# F4_SPI.net
KiCad netlist of a schematic drawn in Altium Designer
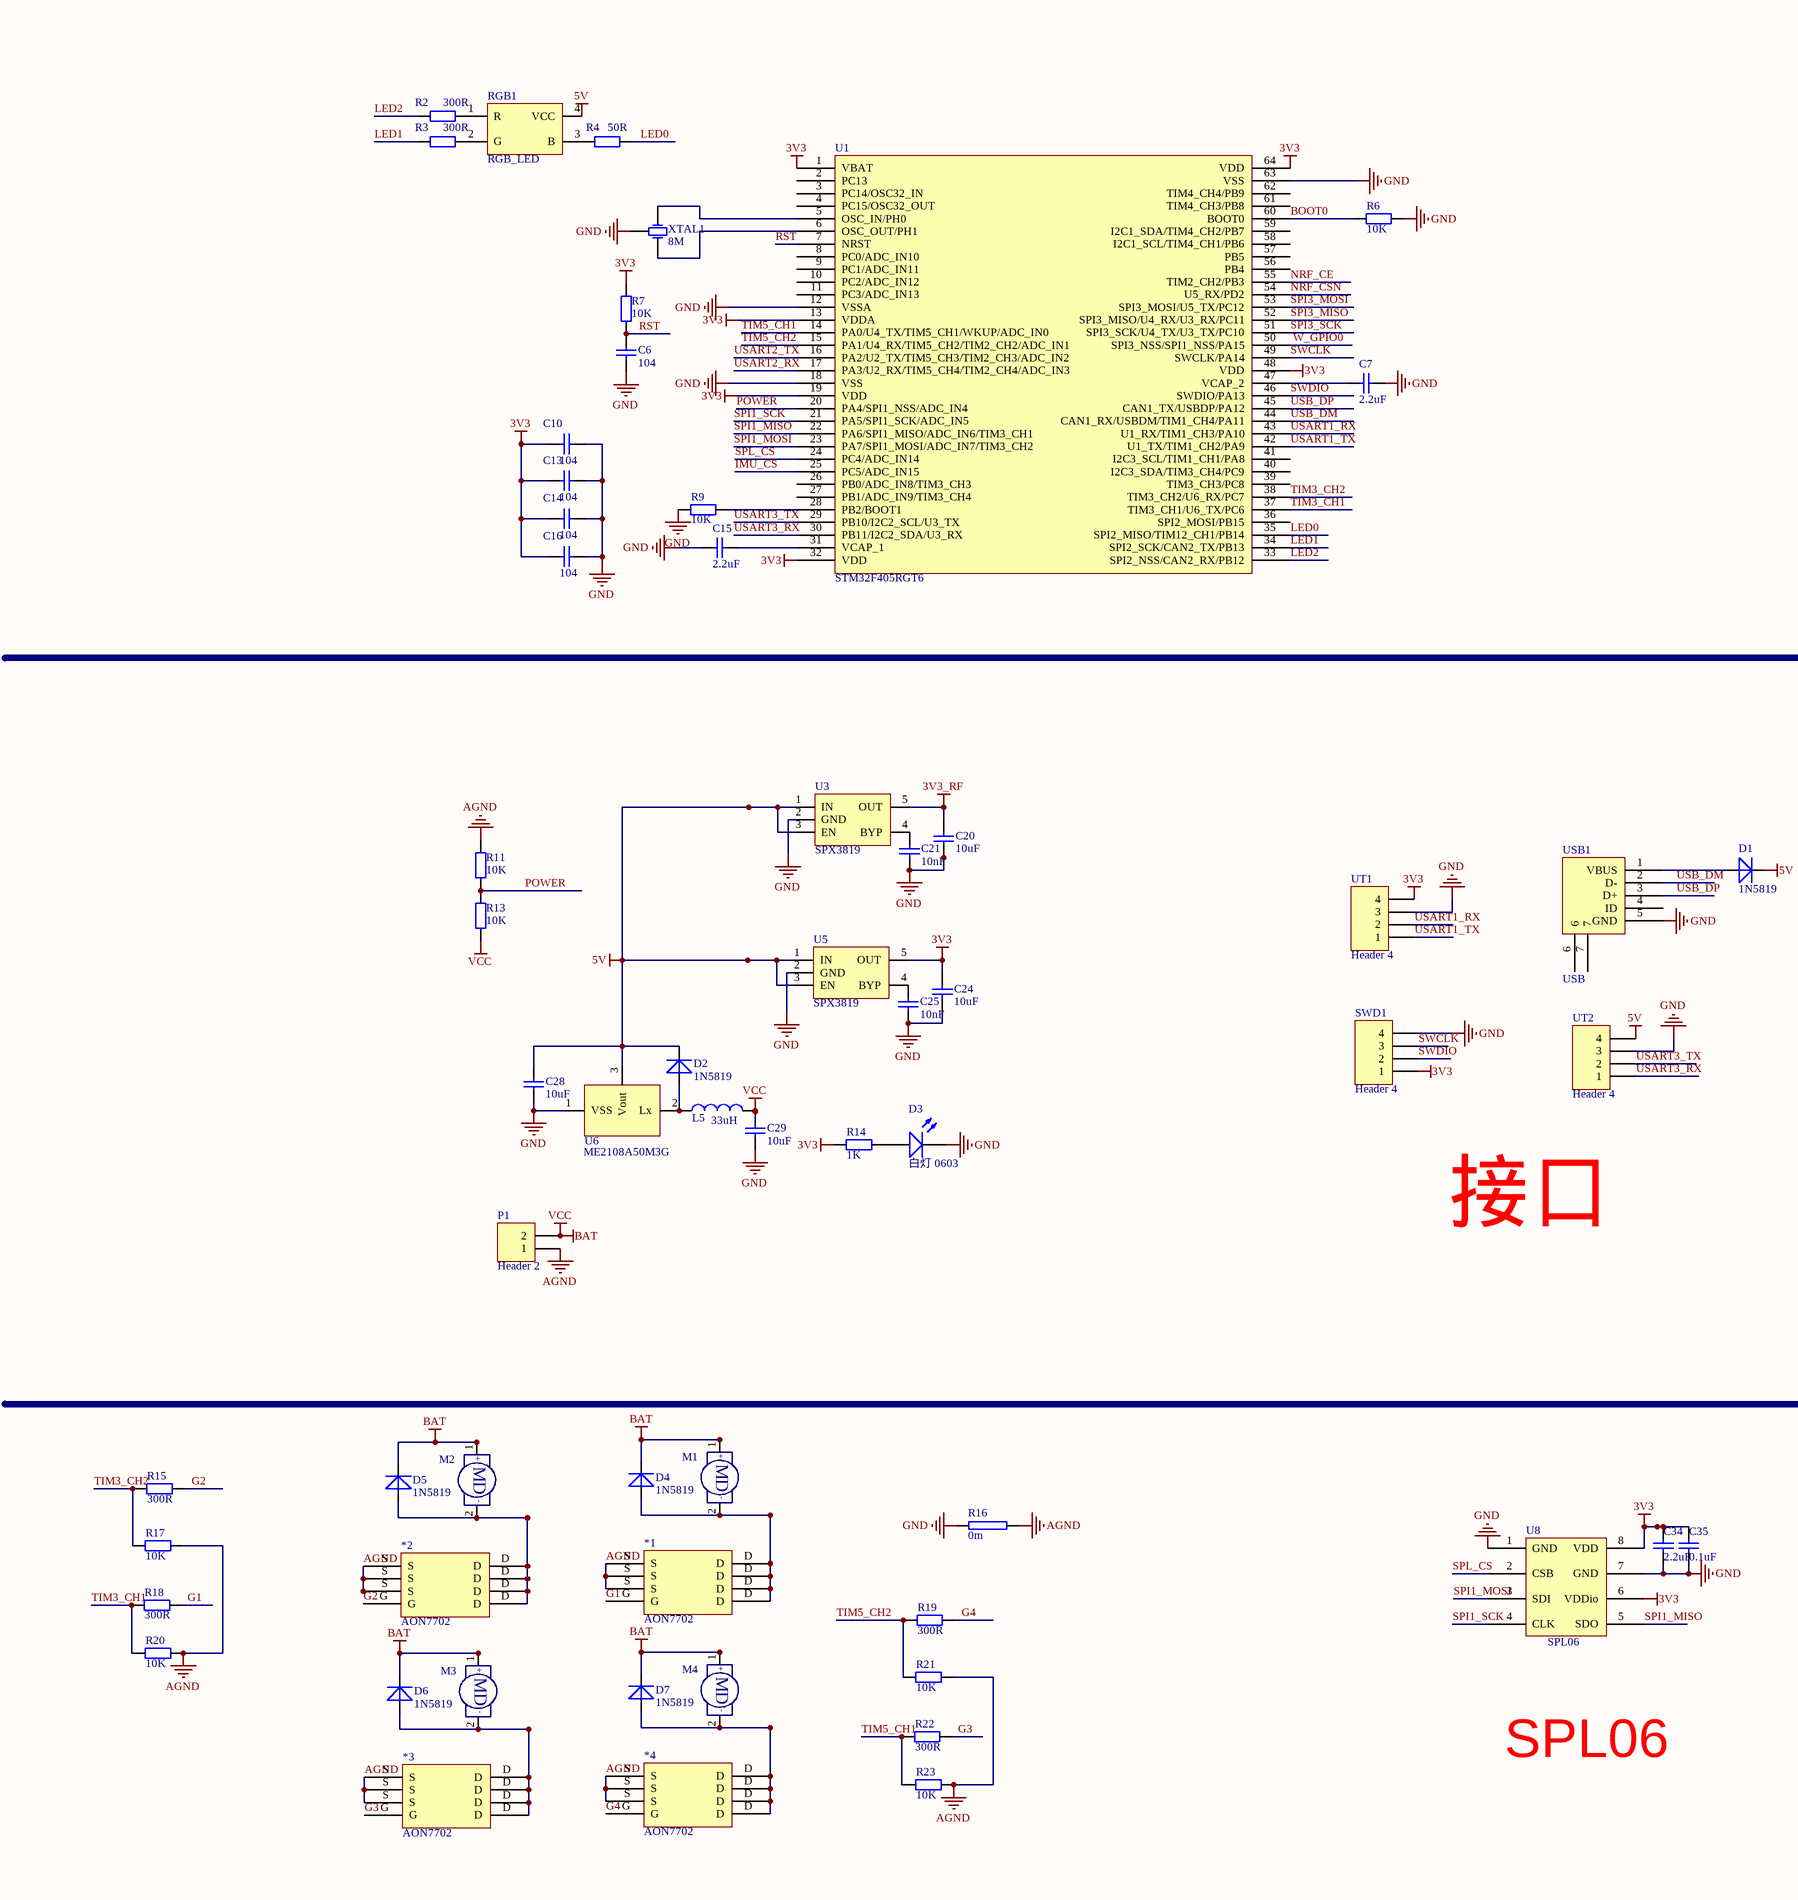
[diagram p0: F4_SPI.SchDoc, left]
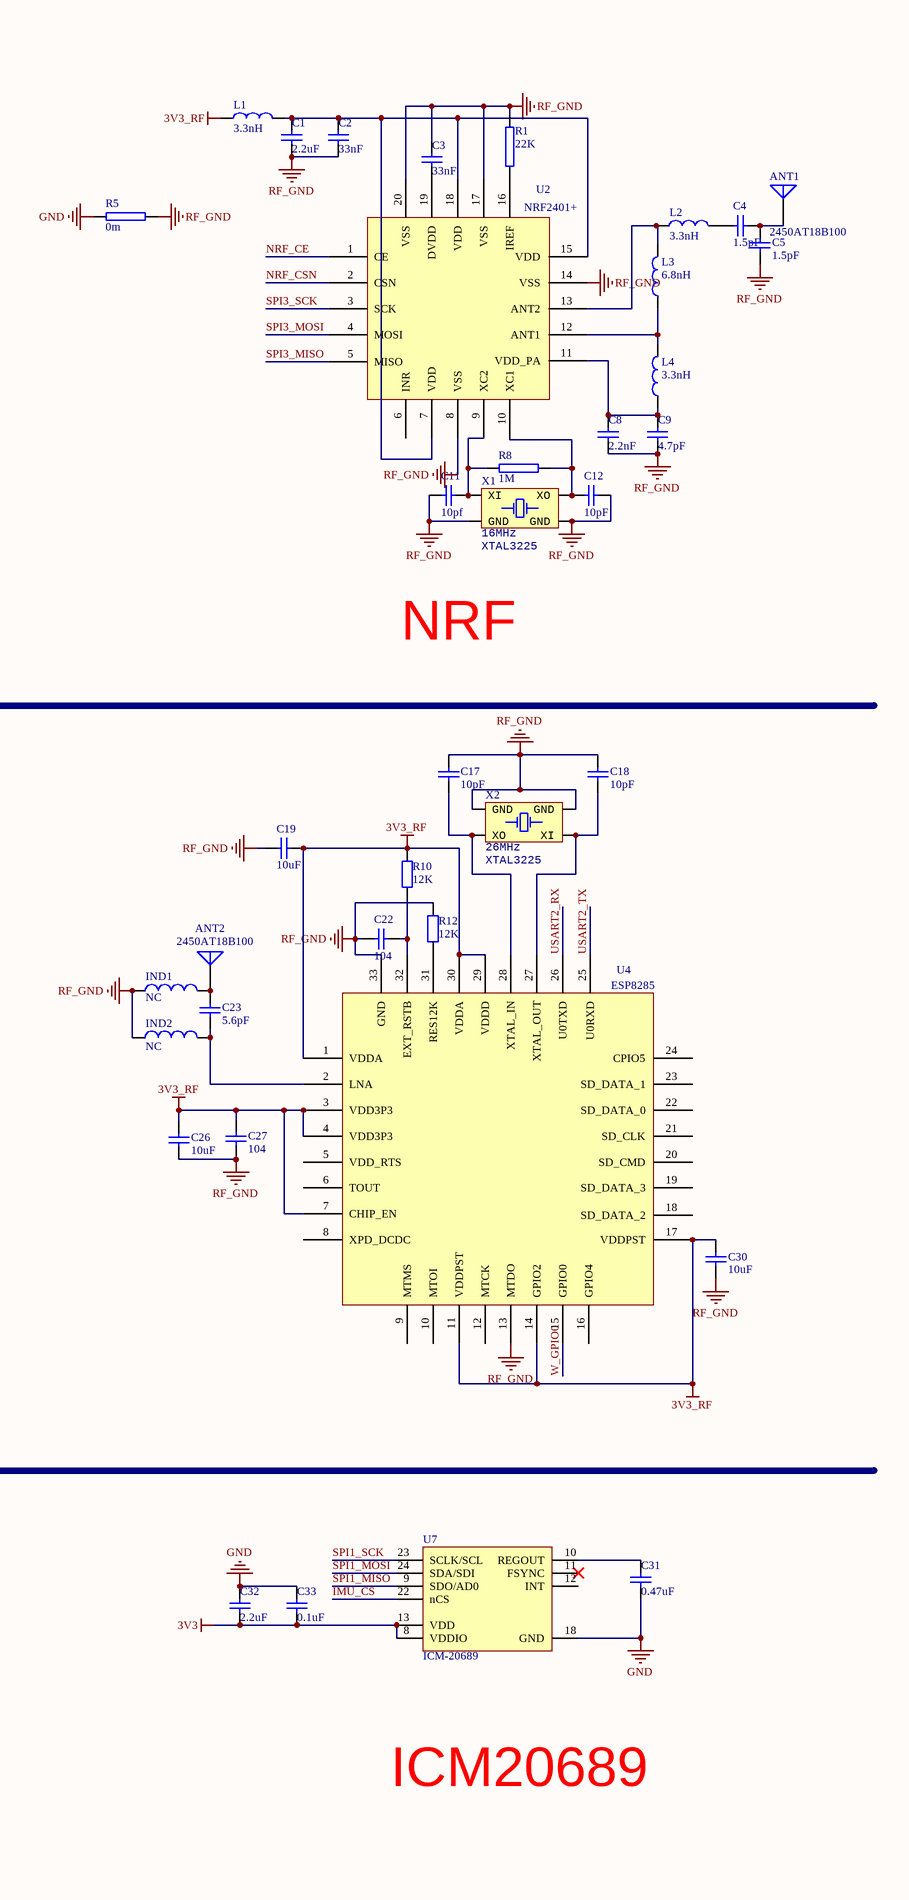
[diagram p1: F4_SPI.SchDoc, right]

(export (version "E")
  (design (tool "Eeschema 10.0.6"))
  (components
    (comp (ref "*1") (value "AON7702") (libsource (lib "XKZ") (part "AON7702")))
    (comp (ref "*2") (value "AON7702") (libsource (lib "XKZ") (part "AON7702")))
    (comp (ref "*3") (value "AON7702") (libsource (lib "XKZ") (part "AON7702")))
    (comp (ref "*4") (value "AON7702") (libsource (lib "XKZ") (part "AON7702")))
    (comp (ref "ANT1")
      (value "2450AT18B100")
      (footprint "2450AT18B100")
      (description "Generic Antenna")
      (libsource (lib "XKZ") (part "Antenna"))
    )
    (comp (ref "ANT2")
      (value "2450AT18B100")
      (footprint "2450AT18B100")
      (description "Generic Antenna")
      (libsource (lib "Miscellaneous Devices") (part "Antenna"))
    )
    (comp (ref "C1")
      (value "2.2uF")
      (footprint "0603_C")
      (description "Capacitor")
      (libsource (lib "Miscellaneous Devices") (part "Cap"))
    )
    (comp (ref "C2")
      (value "33nF")
      (footprint "0603_C")
      (description "Capacitor")
      (libsource (lib "Miscellaneous Devices") (part "Cap"))
    )
    (comp (ref "C3")
      (value "33nF")
      (footprint "0603_C")
      (description "Capacitor")
      (libsource (lib "Miscellaneous Devices") (part "Cap"))
    )
    (comp (ref "C4")
      (value "1.5pF")
      (footprint "0603_C")
      (description "Capacitor")
      (libsource (lib "Miscellaneous Devices") (part "Cap"))
    )
    (comp (ref "C5")
      (value "1.5pF")
      (footprint "0603_C")
      (description "Capacitor")
      (libsource (lib "Miscellaneous Devices") (part "Cap"))
    )
    (comp (ref "C6")
      (value "104")
      (footprint "0603_C")
      (description "Capacitor")
      (libsource (lib "Miscellaneous Devices") (part "Cap"))
    )
    (comp (ref "C7")
      (value "2.2uF")
      (footprint "0603_C")
      (description "Capacitor")
      (libsource (lib "Miscellaneous Devices") (part "Cap"))
    )
    (comp (ref "C8")
      (value "2.2nF")
      (footprint "0603_C")
      (description "Capacitor")
      (libsource (lib "Miscellaneous Devices") (part "Cap"))
    )
    (comp (ref "C9")
      (value "4.7pF")
      (footprint "0603_C")
      (description "Capacitor")
      (libsource (lib "Miscellaneous Devices") (part "Cap"))
    )
    (comp (ref "C10")
      (value "104")
      (footprint "0603_C")
      (description "Capacitor")
      (libsource (lib "Miscellaneous Devices") (part "Cap"))
    )
    (comp (ref "C11")
      (value "10pf")
      (footprint "0603_C")
      (description "Capacitor")
      (fields (field (name "Comment") "10pF"))
      (libsource (lib "Miscellaneous Devices") (part "Cap"))
    )
    (comp (ref "C12")
      (value "10pF")
      (footprint "0603_C")
      (description "Capacitor")
      (libsource (lib "Miscellaneous Devices") (part "Cap"))
    )
    (comp (ref "C13")
      (value "104")
      (footprint "0603_C")
      (description "Capacitor")
      (libsource (lib "Miscellaneous Devices") (part "Cap"))
    )
    (comp (ref "C14")
      (value "104")
      (footprint "0603_C")
      (description "Capacitor")
      (libsource (lib "Miscellaneous Devices") (part "Cap"))
    )
    (comp (ref "C15")
      (value "2.2uF")
      (footprint "0603_C")
      (description "Capacitor")
      (libsource (lib "Miscellaneous Devices") (part "Cap"))
    )
    (comp (ref "C16")
      (value "104")
      (footprint "0603_C")
      (description "Capacitor")
      (libsource (lib "Miscellaneous Devices") (part "Cap"))
    )
    (comp (ref "C17")
      (value "10pF")
      (footprint "0603_C")
      (description "Capacitor")
      (libsource (lib "Miscellaneous Devices") (part "Cap"))
    )
    (comp (ref "C18")
      (value "10pF")
      (footprint "0603_C")
      (description "Capacitor")
      (libsource (lib "Miscellaneous Devices") (part "Cap"))
    )
    (comp (ref "C19")
      (value "10uF")
      (footprint "0603_C")
      (description "Capacitor")
      (fields (field (name "Comment") "10uf"))
      (libsource (lib "Miscellaneous Devices") (part "Cap"))
    )
    (comp (ref "C20")
      (value "10uF")
      (footprint "0603_C")
      (description "Capacitor")
      (libsource (lib "Miscellaneous Devices") (part "Cap"))
    )
    (comp (ref "C21")
      (value "10nF")
      (footprint "0603_C")
      (description "Capacitor")
      (libsource (lib "Miscellaneous Devices") (part "Cap"))
    )
    (comp (ref "C22")
      (value "104")
      (footprint "0603_C")
      (description "Capacitor")
      (libsource (lib "Miscellaneous Devices") (part "Cap"))
    )
    (comp (ref "C23")
      (value "5.6pF")
      (footprint "0603_C")
      (description "Capacitor")
      (libsource (lib "Miscellaneous Devices") (part "Cap"))
    )
    (comp (ref "C24")
      (value "10uF")
      (footprint "0603_C")
      (description "Capacitor")
      (libsource (lib "Miscellaneous Devices") (part "Cap"))
    )
    (comp (ref "C25")
      (value "10nF")
      (footprint "0603_C")
      (description "Capacitor")
      (libsource (lib "Miscellaneous Devices") (part "Cap"))
    )
    (comp (ref "C26")
      (value "10uF")
      (footprint "0603_C")
      (description "Capacitor")
      (libsource (lib "Miscellaneous Devices") (part "Cap"))
    )
    (comp (ref "C27")
      (value "104")
      (footprint "0603_C")
      (description "Capacitor")
      (libsource (lib "Miscellaneous Devices") (part "Cap"))
    )
    (comp (ref "C28")
      (value "10uF")
      (footprint "1206_C")
      (description "Capacitor")
      (libsource (lib "Miscellaneous Devices") (part "Cap"))
    )
    (comp (ref "C29")
      (value "10uF")
      (footprint "1206_C")
      (description "Capacitor")
      (libsource (lib "Miscellaneous Devices") (part "Cap"))
    )
    (comp (ref "C30")
      (value "10uF")
      (footprint "0603_C")
      (description "Capacitor")
      (libsource (lib "Miscellaneous Devices") (part "Cap"))
    )
    (comp (ref "C31")
      (value "0.47uF")
      (footprint "0603_C")
      (description "Capacitor")
      (fields (field (name "Comment") "0.47uf"))
      (libsource (lib "Miscellaneous Devices") (part "Cap"))
    )
    (comp (ref "C32")
      (value "2.2uF")
      (footprint "0603_C")
      (description "Capacitor")
      (fields (field (name "Comment") "10uF"))
      (libsource (lib "Miscellaneous Devices") (part "Cap"))
    )
    (comp (ref "C33")
      (value "0.1uF")
      (footprint "0603_C")
      (description "Capacitor")
      (fields (field (name "Comment") "104"))
      (libsource (lib "Miscellaneous Devices") (part "Cap"))
    )
    (comp (ref "C34")
      (value "2.2uF")
      (footprint "0603_C")
      (description "Capacitor")
      (fields (field (name "Comment") "10uf"))
      (libsource (lib "Miscellaneous Devices") (part "Cap"))
    )
    (comp (ref "C35")
      (value "0.1uF")
      (footprint "0603_C")
      (description "Capacitor")
      (fields (field (name "Comment") "104"))
      (libsource (lib "Miscellaneous Devices") (part "Cap"))
    )
    (comp (ref "D1")
      (value "1N5819")
      (footprint "SOD-323")
      (description "二极管")
      (libsource (lib "NT-SchLibrary") (part "1N4007"))
    )
    (comp (ref "D2")
      (value "1N5819")
      (footprint "SOD-323")
      (description "二极管")
      (libsource (lib "NT-SchLibrary") (part "1N4007"))
    )
    (comp (ref "D3")
      (value "白灯 0603")
      (footprint "0603_LED_S1")
      (description "发光二极管")
      (libsource (lib "Miscellaneous Devices LC") (part "0603 白灯"))
    )
    (comp (ref "D4")
      (value "1N5819")
      (footprint "SOD-323")
      (description "二极管")
      (libsource (lib "NT-SchLibrary") (part "1N4007"))
    )
    (comp (ref "D5")
      (value "1N5819")
      (footprint "SOD-323")
      (description "二极管")
      (libsource (lib "NT-SchLibrary") (part "1N4007"))
    )
    (comp (ref "D6")
      (value "1N5819")
      (footprint "SOD-323")
      (description "二极管")
      (libsource (lib "NT-SchLibrary") (part "1N4007"))
    )
    (comp (ref "D7")
      (value "1N5819")
      (footprint "SOD-323")
      (description "二极管")
      (libsource (lib "NT-SchLibrary") (part "1N4007"))
    )
    (comp (ref "IND1")
      (value "NC")
      (footprint "0603_C")
      (description "Inductor")
      (libsource (lib "Miscellaneous Devices") (part "Inductor"))
    )
    (comp (ref "IND2")
      (value "NC")
      (footprint "0603_C")
      (description "Inductor")
      (libsource (lib "Miscellaneous Devices") (part "Inductor"))
    )
    (comp (ref "L1")
      (value "3.3nH")
      (footprint "0603_L")
      (description "电感")
      (libsource (lib "") (part "L1_1"))
    )
    (comp (ref "L2")
      (value "3.3nH")
      (footprint "0603_L")
      (description "电感")
      (libsource (lib "") (part "L1_1"))
    )
    (comp (ref "L3")
      (value "6.8nH")
      (footprint "0603_L")
      (description "电感")
      (libsource (lib "XKZ") (part "L1"))
    )
    (comp (ref "L4")
      (value "3.3nH")
      (footprint "0603_L")
      (description "电感")
      (libsource (lib "XKZ") (part "L1"))
    )
    (comp (ref "L5")
      (value "33uH")
      (footprint "CD32")
      (description "Inductor")
      (libsource (lib "Miscellaneous Devices") (part "Inductor"))
    )
    (comp (ref "M1")
      (value "Motor")
      (footprint "HDR1X2")
      (description "直流电机")
      (libsource (lib "NT-SchLibrary") (part "Motor"))
    )
    (comp (ref "M2")
      (value "Motor")
      (footprint "HDR1X2")
      (description "直流电机")
      (libsource (lib "NT-SchLibrary") (part "Motor"))
    )
    (comp (ref "M3")
      (value "Motor")
      (footprint "HDR1X2")
      (description "直流电机")
      (libsource (lib "NT-SchLibrary") (part "Motor"))
    )
    (comp (ref "M4")
      (value "Motor")
      (footprint "HDR1X2")
      (description "直流电机")
      (libsource (lib "NT-SchLibrary") (part "Motor"))
    )
    (comp (ref "P1")
      (value "Header 2")
      (footprint "HDR1X2")
      (description "Header, 2-Pin")
      (libsource (lib "FourRotorV2_schlib") (part "Header 2"))
    )
    (comp (ref "R1") (value "22K") (footprint "0603_R") (libsource (lib "XKZ") (part "RES")))
    (comp (ref "R2")
      (value "300R")
      (footprint "0603_R")
      (description "Resistor")
      (fields (field (name "Comment") "1K"))
      (libsource (lib "Miscellaneous Devices") (part "Res2"))
    )
    (comp (ref "R3")
      (value "300R")
      (footprint "0603_R")
      (description "Resistor")
      (fields (field (name "Comment") "1K"))
      (libsource (lib "Miscellaneous Devices") (part "Res2"))
    )
    (comp (ref "R4")
      (value "50R")
      (footprint "0603_R")
      (description "Resistor")
      (fields (field (name "Comment") "1K"))
      (libsource (lib "Miscellaneous Devices") (part "Res2"))
    )
    (comp (ref "R5") (value "0m") (footprint "0603_R") (libsource (lib "XKZ") (part "RES")))
    (comp (ref "R6")
      (value "10K")
      (footprint "0603_R")
      (description "Resistor")
      (libsource (lib "") (part "Res2_1"))
    )
    (comp (ref "R7")
      (value "10K")
      (footprint "0603_R")
      (description "Resistor")
      (libsource (lib "") (part "Res2_2"))
    )
    (comp (ref "R8") (value "1M") (footprint "0603_R") (libsource (lib "XKZ") (part "RES")))
    (comp (ref "R9")
      (value "10K")
      (footprint "0603_R")
      (description "Resistor")
      (libsource (lib "") (part "Res2_1"))
    )
    (comp (ref "R10")
      (value "12K")
      (footprint "0603_R")
      (description "Resistor")
      (libsource (lib "") (part "Res2_2"))
    )
    (comp (ref "R11")
      (value "10K")
      (footprint "0603_R")
      (description "Resistor")
      (libsource (lib "") (part "Res2_2"))
    )
    (comp (ref "R12")
      (value "12K")
      (footprint "0603_R")
      (description "Resistor")
      (libsource (lib "") (part "Res2_2"))
    )
    (comp (ref "R13")
      (value "10K")
      (footprint "0603_R")
      (description "Resistor")
      (libsource (lib "") (part "Res2_2"))
    )
    (comp (ref "R14")
      (value "1K")
      (footprint "0603_R")
      (description "Resistor")
      (libsource (lib "") (part "Res2_1"))
    )
    (comp (ref "R15")
      (value "300R")
      (footprint "0603_R")
      (description "Resistor")
      (libsource (lib "Miscellaneous Devices") (part "Res2"))
    )
    (comp (ref "R16") (value "0m") (footprint "0603_R") (libsource (lib "XKZ") (part "RES")))
    (comp (ref "R17")
      (value "10K")
      (footprint "0603_R")
      (description "Resistor")
      (libsource (lib "Miscellaneous Devices") (part "Res2"))
    )
    (comp (ref "R18")
      (value "300R")
      (footprint "0603_R")
      (description "Resistor")
      (libsource (lib "Miscellaneous Devices") (part "Res2"))
    )
    (comp (ref "R19")
      (value "300R")
      (footprint "0603_R")
      (description "Resistor")
      (libsource (lib "Miscellaneous Devices") (part "Res2"))
    )
    (comp (ref "R20")
      (value "10K")
      (footprint "0603_R")
      (description "Resistor")
      (libsource (lib "Miscellaneous Devices") (part "Res2"))
    )
    (comp (ref "R21")
      (value "10K")
      (footprint "0603_R")
      (description "Resistor")
      (libsource (lib "Miscellaneous Devices") (part "Res2"))
    )
    (comp (ref "R22")
      (value "300R")
      (footprint "0603_R")
      (description "Resistor")
      (libsource (lib "Miscellaneous Devices") (part "Res2"))
    )
    (comp (ref "R23")
      (value "10K")
      (footprint "0603_R")
      (description "Resistor")
      (libsource (lib "Miscellaneous Devices") (part "Res2"))
    )
    (comp (ref "RGB1")
      (value "RGB_LED")
      (footprint "LED_3528_RGB")
      (description "三色高亮LED")
      (libsource (lib "NT-SchLibrary") (part "RGB_LED"))
    )
    (comp (ref "SWD1")
      (value "Header 4")
      (footprint "SIP 1.25")
      (description "Header, 4-Pin")
      (libsource (lib "Miscellaneous Connectors") (part "Header 4"))
    )
    (comp (ref "U1")
      (value "STM32F405RGT6")
      (footprint "LQFP64 10x10_N")
      (description "Flaah:256/RAM:48/IO:51")
      (libsource (lib "ATKF405 V1.1") (part "STM32F405RGT6"))
    )
    (comp (ref "U2")
      (value "NRF2401+")
      (footprint "QFN20 4x4_N")
      (libsource (lib "NT-SchLibrary") (part "NRF2401+"))
    )
    (comp (ref "U3")
      (value "SPX3819")
      (footprint "SOT23-5N")
      (description "3.3V 降压芯片")
      (libsource (lib "NT-SchLibrary") (part "MIC5219"))
    )
    (comp (ref "U4")
      (value "ESP8285")
      (footprint "QFN32 5x5_M")
      (description "ESP8266")
      (libsource (lib "NT-SchLibrary") (part "ESP8266"))
    )
    (comp (ref "U5")
      (value "SPX3819")
      (footprint "SOT23-5N")
      (description "3.3V 降压芯片")
      (libsource (lib "NT-SchLibrary") (part "MIC5219"))
    )
    (comp (ref "U6")
      (value "ME2108A50M3G")
      (footprint "SOT23-3N")
      (description "5升压芯片")
      (libsource (lib "NT-SchLibrary") (part "ME2108A50M3G"))
    )
    (comp (ref "U7")
      (value "ICM-20689")
      (footprint "QFN24 4x4_M")
      (libsource (lib "schlib_by_wjy") (part "ICM-20689"))
    )
    (comp (ref "U8") (value "SPL06") (footprint "BMP280") (libsource (lib "NT-SchLibrary") (part "BMP280")))
    (comp (ref "USB1") (value "USB") (footprint "USB-MICRO_D") (libsource (lib "XKZ") (part "USB")))
    (comp (ref "UT1")
      (value "Header 4")
      (footprint "XKZ:SIP 1.25")
      (description "Header, 4-Pin")
      (libsource (lib "XKZ") (part "Header 4"))
    )
    (comp (ref "UT2")
      (value "Header 4")
      (footprint "SIP 1.25")
      (description "Header, 4-Pin")
      (libsource (lib "XKZ") (part "Header 4"))
    )
    (comp (ref "X1")
      (value "16MHz")
      (footprint "XT_3225_4")
      (description "Crystal Oscillator")
      (fields (field (name "TYPE") "XTAL3225"))
      (libsource (lib "") (part "XTAL_3225_4P_1"))
    )
    (comp (ref "X2")
      (value "26MHz")
      (footprint "XT_3225_4")
      (description "Crystal Oscillator")
      (fields (field (name "TYPE") "XTAL3225"))
      (libsource (lib "XKZ") (part "XTAL_3225_4P"))
    )
    (comp (ref "XTAL1")
      (value "8M")
      (footprint "XTAL-3215-3P")
      (libsource (lib "NT-SchLibrary") (part "XTAL1"))
    )
  )
  (nets
    (net (code "1") (name "/BOOT0") (class "Default")
      (node (ref "R6") (pin "2") (pinfunction "2_2") (pintype "passive"))
      (node (ref "U1") (pin "60") (pinfunction "BOOT0_60") (pintype "passive"))
    )
    (net (code "2") (name "/G1") (class "Default")
      (node (ref "*1") (pin "G") (pinfunction "G_G") (pintype "power_in"))
      (node (ref "R18") (pin "2") (pinfunction "2_2") (pintype "passive"))
    )
    (net (code "3") (name "/G2") (class "Default")
      (node (ref "*2") (pin "G") (pinfunction "G_G") (pintype "power_in"))
      (node (ref "R15") (pin "2") (pinfunction "2_2") (pintype "passive"))
    )
    (net (code "4") (name "/G3") (class "Default")
      (node (ref "*3") (pin "G") (pinfunction "G_G") (pintype "power_in"))
      (node (ref "R22") (pin "2") (pinfunction "2_2") (pintype "passive"))
    )
    (net (code "5") (name "/G4") (class "Default")
      (node (ref "*4") (pin "G") (pinfunction "G_G") (pintype "power_in"))
      (node (ref "R19") (pin "2") (pinfunction "2_2") (pintype "passive"))
    )
    (net (code "6") (name "/IMU_CS") (class "Default")
      (node (ref "U1") (pin "25") (pinfunction "PC5/ADC_IN15_25") (pintype "passive"))
      (node (ref "U7") (pin "22") (pinfunction "nCS_22") (pintype "passive"))
    )
    (net (code "7") (name "/LED0") (class "Default")
      (node (ref "R4") (pin "2") (pinfunction "2_2") (pintype "passive"))
      (node (ref "U1") (pin "35") (pinfunction "SPI2_MISO/TIM12_CH1/PB14_35") (pintype "passive"))
    )
    (net (code "8") (name "/LED1") (class "Default")
      (node (ref "R3") (pin "1") (pinfunction "1_1") (pintype "passive"))
      (node (ref "U1") (pin "34") (pinfunction "SPI2_SCK/CAN2_TX/PB13_34") (pintype "passive"))
    )
    (net (code "9") (name "/LED2") (class "Default")
      (node (ref "R2") (pin "1") (pinfunction "1_1") (pintype "passive"))
      (node (ref "U1") (pin "33") (pinfunction "SPI2_NSS/CAN2_RX/PB12_33") (pintype "passive"))
    )
    (net (code "10") (name "/NRF_CE") (class "Default")
      (node (ref "U1") (pin "55") (pinfunction "TIM2_CH2/PB3_55") (pintype "passive"))
      (node (ref "U2") (pin "1") (pinfunction "CE_1") (pintype "passive"))
    )
    (net (code "11") (name "/NRF_CSN") (class "Default")
      (node (ref "U1") (pin "54") (pinfunction "U5_RX/PD2_54") (pintype "passive"))
      (node (ref "U2") (pin "2") (pinfunction "CSN_2") (pintype "passive"))
    )
    (net (code "12") (name "/POWER") (class "Default")
      (node (ref "R11") (pin "2") (pinfunction "2_2") (pintype "passive"))
      (node (ref "R13") (pin "1") (pinfunction "1_1") (pintype "passive"))
      (node (ref "U1") (pin "20") (pinfunction "PA4/SPI1_NSS/ADC_IN4_20") (pintype "passive"))
    )
    (net (code "13") (name "/RST") (class "Default")
      (node (ref "C6") (pin "1") (pinfunction "1_1") (pintype "passive"))
      (node (ref "R7") (pin "2") (pinfunction "2_2") (pintype "passive"))
      (node (ref "U1") (pin "7") (pinfunction "NRST_7") (pintype "passive"))
    )
    (net (code "14") (name "/SPI1_MISO") (class "Default")
      (node (ref "U1") (pin "22") (pinfunction "PA6/SPI1_MISO/ADC_IN6/TIM3_CH1_22") (pintype "passive"))
      (node (ref "U7") (pin "9") (pinfunction "SDO/AD0_9") (pintype "passive"))
      (node (ref "U8") (pin "5") (pinfunction "SDO_5") (pintype "passive"))
    )
    (net (code "15") (name "/SPI1_MOSI") (class "Default")
      (node (ref "U1") (pin "23") (pinfunction "PA7/SPI1_MOSI/ADC_IN7/TIM3_CH2_23") (pintype "passive"))
      (node (ref "U7") (pin "24") (pinfunction "SDA/SDI_24") (pintype "passive"))
      (node (ref "U8") (pin "3") (pinfunction "SDI_3") (pintype "passive"))
    )
    (net (code "16") (name "/SPI1_SCK") (class "Default")
      (node (ref "U1") (pin "21") (pinfunction "PA5/SPI1_SCK/ADC_IN5_21") (pintype "passive"))
      (node (ref "U7") (pin "23") (pinfunction "SCLK/SCL_23") (pintype "passive"))
      (node (ref "U8") (pin "4") (pinfunction "CLK_4") (pintype "power_in"))
    )
    (net (code "17") (name "/SPI3_MISO") (class "Default")
      (node (ref "U1") (pin "52") (pinfunction "SPI3_MISO/U4_RX/U3_RX/PC11_52") (pintype "passive"))
      (node (ref "U2") (pin "5") (pinfunction "MISO_5") (pintype "power_in"))
    )
    (net (code "18") (name "/SPI3_MOSI") (class "Default")
      (node (ref "U1") (pin "53") (pinfunction "SPI3_MOSI/U5_TX/PC12_53") (pintype "passive"))
      (node (ref "U2") (pin "4") (pinfunction "MOSI_4") (pintype "power_in"))
    )
    (net (code "19") (name "/SPI3_SCK") (class "Default")
      (node (ref "U1") (pin "51") (pinfunction "SPI3_SCK/U4_TX/U3_TX/PC10_51") (pintype "passive"))
      (node (ref "U2") (pin "3") (pinfunction "SCK_3") (pintype "power_in"))
    )
    (net (code "20") (name "/SPL_CS") (class "Default")
      (node (ref "U1") (pin "24") (pinfunction "PC4/ADC_IN14_24") (pintype "passive"))
      (node (ref "U8") (pin "2") (pinfunction "CSB_2") (pintype "passive"))
    )
    (net (code "21") (name "/SWCLK") (class "Default")
      (node (ref "SWD1") (pin "3") (pinfunction "3_3") (pintype "passive"))
      (node (ref "U1") (pin "49") (pinfunction "SWCLK/PA14_49") (pintype "passive"))
    )
    (net (code "22") (name "/SWDIO") (class "Default")
      (node (ref "SWD1") (pin "2") (pinfunction "2_2") (pintype "passive"))
      (node (ref "U1") (pin "46") (pinfunction "SWDIO/PA13_46") (pintype "passive"))
    )
    (net (code "23") (name "/TIM3_CH1") (class "Default")
      (node (ref "R18") (pin "1") (pinfunction "1_1") (pintype "passive"))
      (node (ref "R20") (pin "1") (pinfunction "1_1") (pintype "passive"))
      (node (ref "U1") (pin "37") (pinfunction "TIM3_CH1/U6_TX/PC6_37") (pintype "passive"))
    )
    (net (code "24") (name "/TIM3_CH2") (class "Default")
      (node (ref "R15") (pin "1") (pinfunction "1_1") (pintype "passive"))
      (node (ref "R17") (pin "1") (pinfunction "1_1") (pintype "passive"))
      (node (ref "U1") (pin "38") (pinfunction "TIM3_CH2/U6_RX/PC7_38") (pintype "passive"))
    )
    (net (code "25") (name "/TIM5_CH1") (class "Default")
      (node (ref "R22") (pin "1") (pinfunction "1_1") (pintype "passive"))
      (node (ref "R23") (pin "1") (pinfunction "1_1") (pintype "passive"))
      (node (ref "U1") (pin "14") (pinfunction "PA0/U4_TX/TIM5_CH1/WKUP/ADC_IN0_14") (pintype "passive"))
    )
    (net (code "26") (name "/TIM5_CH2") (class "Default")
      (node (ref "R19") (pin "1") (pinfunction "1_1") (pintype "passive"))
      (node (ref "R21") (pin "1") (pinfunction "1_1") (pintype "passive"))
      (node (ref "U1") (pin "15") (pinfunction "PA1/U4_RX/TIM5_CH2/TIM2_CH2/ADC_IN1_15") (pintype "passive"))
    )
    (net (code "27") (name "/USART1_RX") (class "Default")
      (node (ref "U1") (pin "43") (pinfunction "U1_RX/TIM1_CH3/PA10_43") (pintype "passive"))
      (node (ref "UT1") (pin "2") (pinfunction "2_2") (pintype "passive"))
    )
    (net (code "28") (name "/USART1_TX") (class "Default")
      (node (ref "U1") (pin "42") (pinfunction "U1_TX/TIM1_CH2/PA9_42") (pintype "passive"))
      (node (ref "UT1") (pin "1") (pinfunction "1_1") (pintype "passive"))
    )
    (net (code "29") (name "/USART2_RX") (class "Default")
      (node (ref "U1") (pin "17") (pinfunction "PA3/U2_RX/TIM5_CH4/TIM2_CH4/ADC_IN3_17") (pintype "passive"))
      (node (ref "U4") (pin "26") (pinfunction "U0TXD_26") (pintype "power_in"))
    )
    (net (code "30") (name "/USART2_TX") (class "Default")
      (node (ref "U1") (pin "16") (pinfunction "PA2/U2_TX/TIM5_CH3/TIM2_CH3/ADC_IN2_16") (pintype "passive"))
      (node (ref "U4") (pin "25") (pinfunction "U0RXD_25") (pintype "power_in"))
    )
    (net (code "31") (name "/USART3_RX") (class "Default")
      (node (ref "U1") (pin "30") (pinfunction "PB11/I2C2_SDA/U3_RX_30") (pintype "passive"))
      (node (ref "UT2") (pin "1") (pinfunction "1_1") (pintype "passive"))
    )
    (net (code "32") (name "/USART3_TX") (class "Default")
      (node (ref "U1") (pin "29") (pinfunction "PB10/I2C2_SCL/U3_TX_29") (pintype "passive"))
      (node (ref "UT2") (pin "2") (pinfunction "2_2") (pintype "passive"))
    )
    (net (code "33") (name "/USB_DM") (class "Default")
      (node (ref "U1") (pin "44") (pinfunction "CAN1_RX/USBDM/TIM1_CH4/PA11_44") (pintype "passive"))
      (node (ref "USB1") (pin "2") (pinfunction "D-_2") (pintype "passive"))
    )
    (net (code "34") (name "/USB_DP") (class "Default")
      (node (ref "U1") (pin "45") (pinfunction "CAN1_TX/USBDP/PA12_45") (pintype "passive"))
      (node (ref "USB1") (pin "3") (pinfunction "D+_3") (pintype "passive"))
    )
    (net (code "35") (name "/W_GPIO0") (class "Default")
      (node (ref "U1") (pin "50") (pinfunction "SPI3_NSS/SPI1_NSS/PA15_50") (pintype "passive"))
      (node (ref "U4") (pin "15") (pinfunction "GPIO0_15") (pintype "power_in"))
    )
    (net (code "36") (name "3V3") (class "Default")
      (node (ref "C10") (pin "2") (pinfunction "2_2") (pintype "passive"))
      (node (ref "C13") (pin "2") (pinfunction "2_2") (pintype "passive"))
      (node (ref "C14") (pin "2") (pinfunction "2_2") (pintype "passive"))
      (node (ref "C16") (pin "2") (pinfunction "2_2") (pintype "passive"))
      (node (ref "C24") (pin "1") (pinfunction "1_1") (pintype "passive"))
      (node (ref "C32") (pin "1") (pinfunction "1_1") (pintype "passive"))
      (node (ref "C33") (pin "1") (pinfunction "1_1") (pintype "passive"))
      (node (ref "C34") (pin "2") (pinfunction "2_2") (pintype "passive"))
      (node (ref "C35") (pin "2") (pinfunction "2_2") (pintype "passive"))
      (node (ref "R14") (pin "2") (pinfunction "2_2") (pintype "passive"))
      (node (ref "R7") (pin "1") (pinfunction "1_1") (pintype "passive"))
      (node (ref "SWD1") (pin "1") (pinfunction "1_1") (pintype "passive"))
      (node (ref "U1") (pin "1") (pinfunction "VBAT_1") (pintype "passive"))
      (node (ref "U1") (pin "13") (pinfunction "VDDA_13") (pintype "passive"))
      (node (ref "U1") (pin "19") (pinfunction "VDD_19") (pintype "passive"))
      (node (ref "U1") (pin "32") (pinfunction "VDD_32") (pintype "passive"))
      (node (ref "U1") (pin "48") (pinfunction "VDD_48") (pintype "passive"))
      (node (ref "U1") (pin "64") (pinfunction "VDD_64") (pintype "passive"))
      (node (ref "U5") (pin "5") (pinfunction "OUT_5") (pintype "passive"))
      (node (ref "U7") (pin "13") (pinfunction "VDD_13") (pintype "passive"))
      (node (ref "U7") (pin "8") (pinfunction "VDDIO_8") (pintype "passive"))
      (node (ref "U8") (pin "6") (pinfunction "VDDio_6") (pintype "passive"))
      (node (ref "U8") (pin "8") (pinfunction "VDD_8") (pintype "power_in"))
      (node (ref "UT1") (pin "4") (pinfunction "4_4") (pintype "passive"))
    )
    (net (code "37") (name "3V3_RF") (class "Default")
      (node (ref "C19") (pin "2") (pinfunction "2_2") (pintype "passive"))
      (node (ref "C20") (pin "1") (pinfunction "1_1") (pintype "passive"))
      (node (ref "C26") (pin "1") (pinfunction "1_1") (pintype "passive"))
      (node (ref "C27") (pin "1") (pinfunction "1_1") (pintype "passive"))
      (node (ref "C30") (pin "1") (pinfunction "1_1") (pintype "passive"))
      (node (ref "L1") (pin "2") (pinfunction "2_2") (pintype "passive"))
      (node (ref "R10") (pin "1") (pinfunction "1_1") (pintype "passive"))
      (node (ref "U3") (pin "5") (pinfunction "OUT_5") (pintype "passive"))
      (node (ref "U4") (pin "1") (pinfunction "VDDA_1") (pintype "passive"))
      (node (ref "U4") (pin "11") (pinfunction "VDDPST_11") (pintype "power_in"))
      (node (ref "U4") (pin "14") (pinfunction "GPIO2_14") (pintype "power_in"))
      (node (ref "U4") (pin "17") (pinfunction "VDDPST_17") (pintype "power_in"))
      (node (ref "U4") (pin "29") (pinfunction "VDDD_29") (pintype "power_in"))
      (node (ref "U4") (pin "3") (pinfunction "VDD3P3_3") (pintype "power_in"))
      (node (ref "U4") (pin "30") (pinfunction "VDDA_30") (pintype "power_in"))
      (node (ref "U4") (pin "4") (pinfunction "VDD3P3_4") (pintype "power_in"))
      (node (ref "U4") (pin "7") (pinfunction "CHIP_EN_7") (pintype "power_in"))
    )
    (net (code "38") (name "5V") (class "Default")
      (node (ref "C28") (pin "1") (pinfunction "1_1") (pintype "passive"))
      (node (ref "D1") (pin "2") (pinfunction "2_2") (pintype "passive"))
      (node (ref "D2") (pin "2") (pinfunction "2_2") (pintype "passive"))
      (node (ref "RGB1") (pin "4") (pinfunction "VCC_4") (pintype "passive"))
      (node (ref "U3") (pin "1") (pinfunction "IN_1") (pintype "passive"))
      (node (ref "U3") (pin "3") (pinfunction "EN_3") (pintype "passive"))
      (node (ref "U5") (pin "1") (pinfunction "IN_1") (pintype "passive"))
      (node (ref "U5") (pin "3") (pinfunction "EN_3") (pintype "passive"))
      (node (ref "U6") (pin "3") (pinfunction "Vout_3") (pintype "passive"))
      (node (ref "UT2") (pin "4") (pinfunction "4_4") (pintype "passive"))
    )
    (net (code "39") (name "AGND") (class "Default")
      (node (ref "*1") (pin "S") (pinfunction "S_S") (pintype "passive"))
      (node (ref "*2") (pin "S") (pinfunction "S_S") (pintype "passive"))
      (node (ref "*3") (pin "S") (pinfunction "S_S") (pintype "passive"))
      (node (ref "*4") (pin "S") (pinfunction "S_S") (pintype "passive"))
      (node (ref "P1") (pin "1") (pinfunction "1_1") (pintype "passive"))
      (node (ref "R11") (pin "1") (pinfunction "1_1") (pintype "passive"))
      (node (ref "R16") (pin "1") (pinfunction "1_1") (pintype "passive"))
      (node (ref "R17") (pin "2") (pinfunction "2_2") (pintype "passive"))
      (node (ref "R20") (pin "2") (pinfunction "2_2") (pintype "passive"))
      (node (ref "R21") (pin "2") (pinfunction "2_2") (pintype "passive"))
      (node (ref "R23") (pin "2") (pinfunction "2_2") (pintype "passive"))
    )
    (net (code "40") (name "BAT") (class "Default")
      (node (ref "C29") (pin "1") (pinfunction "1_1") (pintype "passive"))
      (node (ref "D4") (pin "2") (pinfunction "2_2") (pintype "passive"))
      (node (ref "D5") (pin "2") (pinfunction "2_2") (pintype "passive"))
      (node (ref "D6") (pin "2") (pinfunction "2_2") (pintype "passive"))
      (node (ref "D7") (pin "2") (pinfunction "2_2") (pintype "passive"))
      (node (ref "L5") (pin "2") (pinfunction "2_2") (pintype "passive"))
      (node (ref "M1") (pin "1") (pinfunction "1_1") (pintype "passive"))
      (node (ref "M2") (pin "1") (pinfunction "1_1") (pintype "passive"))
      (node (ref "M3") (pin "1") (pinfunction "1_1") (pintype "passive"))
      (node (ref "M4") (pin "1") (pinfunction "1_1") (pintype "passive"))
      (node (ref "P1") (pin "2") (pinfunction "2_2") (pintype "passive"))
      (node (ref "R13") (pin "2") (pinfunction "2_2") (pintype "passive"))
    )
    (net (code "41") (name "GND") (class "Default")
      (node (ref "C10") (pin "1") (pinfunction "1_1") (pintype "passive"))
      (node (ref "C13") (pin "1") (pinfunction "1_1") (pintype "passive"))
      (node (ref "C14") (pin "1") (pinfunction "1_1") (pintype "passive"))
      (node (ref "C15") (pin "2") (pinfunction "2_2") (pintype "passive"))
      (node (ref "C16") (pin "1") (pinfunction "1_1") (pintype "passive"))
      (node (ref "C20") (pin "2") (pinfunction "2_2") (pintype "passive"))
      (node (ref "C21") (pin "2") (pinfunction "2_2") (pintype "passive"))
      (node (ref "C24") (pin "2") (pinfunction "2_2") (pintype "passive"))
      (node (ref "C25") (pin "2") (pinfunction "2_2") (pintype "passive"))
      (node (ref "C28") (pin "2") (pinfunction "2_2") (pintype "passive"))
      (node (ref "C29") (pin "2") (pinfunction "2_2") (pintype "passive"))
      (node (ref "C31") (pin "1") (pinfunction "1_1") (pintype "passive"))
      (node (ref "C32") (pin "2") (pinfunction "2_2") (pintype "passive"))
      (node (ref "C33") (pin "2") (pinfunction "2_2") (pintype "passive"))
      (node (ref "C34") (pin "1") (pinfunction "1_1") (pintype "passive"))
      (node (ref "C35") (pin "1") (pinfunction "1_1") (pintype "passive"))
      (node (ref "C6") (pin "2") (pinfunction "2_2") (pintype "passive"))
      (node (ref "C7") (pin "1") (pinfunction "1_1") (pintype "passive"))
      (node (ref "D3") (pin "K") (pinfunction "K_K") (pintype "passive"))
      (node (ref "R16") (pin "2") (pinfunction "2_2") (pintype "passive"))
      (node (ref "R5") (pin "2") (pinfunction "2_2") (pintype "passive"))
      (node (ref "R6") (pin "1") (pinfunction "1_1") (pintype "passive"))
      (node (ref "R9") (pin "2") (pinfunction "2_2") (pintype "passive"))
      (node (ref "SWD1") (pin "4") (pinfunction "4_4") (pintype "passive"))
      (node (ref "U1") (pin "12") (pinfunction "VSSA_12") (pintype "passive"))
      (node (ref "U1") (pin "18") (pinfunction "VSS_18") (pintype "passive"))
      (node (ref "U1") (pin "63") (pinfunction "VSS_63") (pintype "passive"))
      (node (ref "U3") (pin "2") (pinfunction "GND_2") (pintype "passive"))
      (node (ref "U5") (pin "2") (pinfunction "GND_2") (pintype "passive"))
      (node (ref "U6") (pin "1") (pinfunction "VSS_1") (pintype "passive"))
      (node (ref "U7") (pin "18") (pinfunction "GND_18") (pintype "passive"))
      (node (ref "U8") (pin "1") (pinfunction "GND_1") (pintype "passive"))
      (node (ref "U8") (pin "7") (pinfunction "GND_7") (pintype "passive"))
      (node (ref "USB1") (pin "5") (pinfunction "GND_5") (pintype "passive"))
      (node (ref "UT1") (pin "3") (pinfunction "3_3") (pintype "passive"))
      (node (ref "UT2") (pin "3") (pinfunction "3_3") (pintype "passive"))
      (node (ref "XTAL1") (pin "2") (pinfunction "2_2") (pintype "passive"))
    )
    (net (code "42") (name "Net-(*1-PadD)") (class "Default")
      (node (ref "*1") (pin "D") (pinfunction "D_D") (pintype "power_in"))
      (node (ref "D4") (pin "1") (pinfunction "1_1") (pintype "passive"))
      (node (ref "M1") (pin "2") (pinfunction "2_2") (pintype "passive"))
    )
    (net (code "43") (name "Net-(*2-PadD)") (class "Default")
      (node (ref "*2") (pin "D") (pinfunction "D_D") (pintype "power_in"))
      (node (ref "D5") (pin "1") (pinfunction "1_1") (pintype "passive"))
      (node (ref "M2") (pin "2") (pinfunction "2_2") (pintype "passive"))
    )
    (net (code "44") (name "Net-(*3-PadD)") (class "Default")
      (node (ref "*3") (pin "D") (pinfunction "D_D") (pintype "power_in"))
      (node (ref "D6") (pin "1") (pinfunction "1_1") (pintype "passive"))
      (node (ref "M3") (pin "2") (pinfunction "2_2") (pintype "passive"))
    )
    (net (code "45") (name "Net-(*4-PadD)") (class "Default")
      (node (ref "*4") (pin "D") (pinfunction "D_D") (pintype "power_in"))
      (node (ref "D7") (pin "1") (pinfunction "1_1") (pintype "passive"))
      (node (ref "M4") (pin "2") (pinfunction "2_2") (pintype "passive"))
    )
    (net (code "46") (name "Net-(ANT1-A)") (class "Default")
      (node (ref "ANT1") (pin "1") (pinfunction "A_1") (pintype "passive"))
      (node (ref "C4") (pin "1") (pinfunction "1_1") (pintype "passive"))
      (node (ref "C5") (pin "1") (pinfunction "1_1") (pintype "passive"))
    )
    (net (code "47") (name "Net-(ANT2-A)") (class "Default")
      (node (ref "ANT2") (pin "1") (pinfunction "A_1") (pintype "passive"))
      (node (ref "C23") (pin "1") (pinfunction "1_1") (pintype "passive"))
      (node (ref "IND1") (pin "2") (pinfunction "2_2") (pintype "passive"))
    )
    (net (code "48") (name "Net-(C1-Pad2)") (class "Default")
      (node (ref "C1") (pin "2") (pinfunction "2_2") (pintype "passive"))
      (node (ref "C2") (pin "2") (pinfunction "2_2") (pintype "passive"))
      (node (ref "L1") (pin "1") (pinfunction "1_1") (pintype "passive"))
      (node (ref "U2") (pin "15") (pinfunction "VDD_15") (pintype "passive"))
      (node (ref "U2") (pin "18") (pinfunction "VDD_18") (pintype "power_in"))
      (node (ref "U2") (pin "7") (pinfunction "VDD_7") (pintype "power_in"))
    )
    (net (code "49") (name "Net-(C4-Pad2)") (class "Default")
      (node (ref "C4") (pin "2") (pinfunction "2_2") (pintype "passive"))
      (node (ref "L2") (pin "1") (pinfunction "1_1") (pintype "passive"))
    )
    (net (code "50") (name "Net-(D3-PadA)") (class "Default")
      (node (ref "D3") (pin "A") (pinfunction "A_A") (pintype "passive"))
      (node (ref "R14") (pin "1") (pinfunction "1_1") (pintype "passive"))
    )
    (net (code "51") (name "Net-(RGB1-B)") (class "Default")
      (node (ref "R4") (pin "1") (pinfunction "1_1") (pintype "passive"))
      (node (ref "RGB1") (pin "3") (pinfunction "B_3") (pintype "passive"))
    )
    (net (code "52") (name "Net-(RGB1-G)") (class "Default")
      (node (ref "R3") (pin "2") (pinfunction "2_2") (pintype "passive"))
      (node (ref "RGB1") (pin "2") (pinfunction "G_2") (pintype "passive"))
    )
    (net (code "53") (name "Net-(RGB1-R)") (class "Default")
      (node (ref "R2") (pin "2") (pinfunction "2_2") (pintype "passive"))
      (node (ref "RGB1") (pin "1") (pinfunction "R_1") (pintype "passive"))
    )
    (net (code "54") (name "Net-(U1-OSC_IN{slash}PH0)") (class "Default")
      (node (ref "U1") (pin "5") (pinfunction "OSC_IN/PH0_5") (pintype "passive"))
      (node (ref "XTAL1") (pin "1") (pinfunction "1_1") (pintype "passive"))
    )
    (net (code "55") (name "Net-(U1-OSC_OUT{slash}PH1)") (class "Default")
      (node (ref "U1") (pin "6") (pinfunction "OSC_OUT/PH1_6") (pintype "passive"))
      (node (ref "XTAL1") (pin "3") (pinfunction "3_3") (pintype "passive"))
    )
    (net (code "56") (name "Net-(U1-PB2{slash}BOOT1)") (class "Default")
      (node (ref "R9") (pin "1") (pinfunction "1_1") (pintype "passive"))
      (node (ref "U1") (pin "28") (pinfunction "PB2/BOOT1_28") (pintype "passive"))
    )
    (net (code "57") (name "Net-(U1-VCAP_1)") (class "Default")
      (node (ref "C15") (pin "1") (pinfunction "1_1") (pintype "passive"))
      (node (ref "U1") (pin "31") (pinfunction "VCAP_1_31") (pintype "passive"))
    )
    (net (code "58") (name "Net-(U1-VCAP_2)") (class "Default")
      (node (ref "C7") (pin "2") (pinfunction "2_2") (pintype "passive"))
      (node (ref "U1") (pin "47") (pinfunction "VCAP_2_47") (pintype "passive"))
    )
    (net (code "59") (name "Net-(U2-ANT1)") (class "Default")
      (node (ref "L3") (pin "2") (pinfunction "2_2") (pintype "passive"))
      (node (ref "L4") (pin "1") (pinfunction "1_1") (pintype "passive"))
      (node (ref "U2") (pin "12") (pinfunction "ANT1_12") (pintype "passive"))
    )
    (net (code "60") (name "Net-(U2-ANT2)") (class "Default")
      (node (ref "L2") (pin "2") (pinfunction "2_2") (pintype "passive"))
      (node (ref "L3") (pin "1") (pinfunction "1_1") (pintype "passive"))
      (node (ref "U2") (pin "13") (pinfunction "ANT2_13") (pintype "passive"))
    )
    (net (code "61") (name "Net-(U2-DVDD)") (class "Default")
      (node (ref "C3") (pin "1") (pinfunction "1_1") (pintype "passive"))
      (node (ref "U2") (pin "19") (pinfunction "DVDD_19") (pintype "power_in"))
    )
    (net (code "62") (name "Net-(U2-IREF)") (class "Default")
      (node (ref "R1") (pin "1") (pinfunction "1_1") (pintype "passive"))
      (node (ref "U2") (pin "16") (pinfunction "IREF_16") (pintype "power_in"))
    )
    (net (code "63") (name "Net-(U2-VDD_PA)") (class "Default")
      (node (ref "C8") (pin "2") (pinfunction "2_2") (pintype "passive"))
      (node (ref "C9") (pin "2") (pinfunction "2_2") (pintype "passive"))
      (node (ref "L4") (pin "2") (pinfunction "2_2") (pintype "passive"))
      (node (ref "U2") (pin "11") (pinfunction "VDD_PA_11") (pintype "power_in"))
    )
    (net (code "64") (name "Net-(U2-XC1)") (class "Default")
      (node (ref "C12") (pin "2") (pinfunction "2_2") (pintype "passive"))
      (node (ref "R8") (pin "1") (pinfunction "1_1") (pintype "passive"))
      (node (ref "U2") (pin "10") (pinfunction "XC1_10") (pintype "power_in"))
      (node (ref "X1") (pin "3") (pinfunction "XO_3") (pintype "passive"))
    )
    (net (code "65") (name "Net-(U2-XC2)") (class "Default")
      (node (ref "C11") (pin "1") (pinfunction "1_1") (pintype "passive"))
      (node (ref "R8") (pin "2") (pinfunction "2_2") (pintype "passive"))
      (node (ref "U2") (pin "9") (pinfunction "XC2_9") (pintype "power_in"))
      (node (ref "X1") (pin "1") (pinfunction "XI_1") (pintype "passive"))
    )
    (net (code "66") (name "Net-(U3-BYP)") (class "Default")
      (node (ref "C21") (pin "1") (pinfunction "1_1") (pintype "passive"))
      (node (ref "U3") (pin "4") (pinfunction "BYP_4") (pintype "passive"))
    )
    (net (code "67") (name "Net-(U4-EXT_RSTB)") (class "Default")
      (node (ref "C22") (pin "2") (pinfunction "2_2") (pintype "passive"))
      (node (ref "R10") (pin "2") (pinfunction "2_2") (pintype "passive"))
      (node (ref "U4") (pin "32") (pinfunction "EXT_RSTB_32") (pintype "power_in"))
    )
    (net (code "68") (name "Net-(U4-LNA)") (class "Default")
      (node (ref "C23") (pin "2") (pinfunction "2_2") (pintype "passive"))
      (node (ref "IND2") (pin "2") (pinfunction "2_2") (pintype "passive"))
      (node (ref "U4") (pin "2") (pinfunction "LNA_2") (pintype "passive"))
    )
    (net (code "69") (name "Net-(U4-RES12K)") (class "Default")
      (node (ref "R12") (pin "2") (pinfunction "2_2") (pintype "passive"))
      (node (ref "U4") (pin "31") (pinfunction "RES12K_31") (pintype "power_in"))
    )
    (net (code "70") (name "Net-(U4-XTAL_IN)") (class "Default")
      (node (ref "C17") (pin "2") (pinfunction "2_2") (pintype "passive"))
      (node (ref "U4") (pin "28") (pinfunction "XTAL_IN_28") (pintype "power_in"))
      (node (ref "X2") (pin "3") (pinfunction "XO_3") (pintype "passive"))
    )
    (net (code "71") (name "Net-(U4-XTAL_OUT)") (class "Default")
      (node (ref "C18") (pin "2") (pinfunction "2_2") (pintype "passive"))
      (node (ref "U4") (pin "27") (pinfunction "XTAL_OUT_27") (pintype "power_in"))
      (node (ref "X2") (pin "1") (pinfunction "XI_1") (pintype "passive"))
    )
    (net (code "72") (name "Net-(U5-BYP)") (class "Default")
      (node (ref "C25") (pin "1") (pinfunction "1_1") (pintype "passive"))
      (node (ref "U5") (pin "4") (pinfunction "BYP_4") (pintype "passive"))
    )
    (net (code "73") (name "Net-(U6-Lx)") (class "Default")
      (node (ref "D2") (pin "1") (pinfunction "1_1") (pintype "passive"))
      (node (ref "L5") (pin "1") (pinfunction "1_1") (pintype "passive"))
      (node (ref "U6") (pin "2") (pinfunction "Lx_2") (pintype "passive"))
    )
    (net (code "74") (name "Net-(U7-REGOUT)") (class "Default")
      (node (ref "C31") (pin "2") (pinfunction "2_2") (pintype "passive"))
      (node (ref "U7") (pin "10") (pinfunction "REGOUT_10") (pintype "passive"))
    )
    (net (code "75") (name "Net-(USB1-VBUS)") (class "Default")
      (node (ref "D1") (pin "1") (pinfunction "1_1") (pintype "passive"))
      (node (ref "USB1") (pin "1") (pinfunction "VBUS_1") (pintype "passive"))
    )
    (net (code "76") (name "RF_GND") (class "Default")
      (node (ref "C1") (pin "1") (pinfunction "1_1") (pintype "passive"))
      (node (ref "C11") (pin "2") (pinfunction "2_2") (pintype "passive"))
      (node (ref "C12") (pin "1") (pinfunction "1_1") (pintype "passive"))
      (node (ref "C17") (pin "1") (pinfunction "1_1") (pintype "passive"))
      (node (ref "C18") (pin "1") (pinfunction "1_1") (pintype "passive"))
      (node (ref "C19") (pin "1") (pinfunction "1_1") (pintype "passive"))
      (node (ref "C2") (pin "1") (pinfunction "1_1") (pintype "passive"))
      (node (ref "C22") (pin "1") (pinfunction "1_1") (pintype "passive"))
      (node (ref "C26") (pin "2") (pinfunction "2_2") (pintype "passive"))
      (node (ref "C27") (pin "2") (pinfunction "2_2") (pintype "passive"))
      (node (ref "C3") (pin "2") (pinfunction "2_2") (pintype "passive"))
      (node (ref "C30") (pin "2") (pinfunction "2_2") (pintype "passive"))
      (node (ref "C5") (pin "2") (pinfunction "2_2") (pintype "passive"))
      (node (ref "C8") (pin "1") (pinfunction "1_1") (pintype "passive"))
      (node (ref "C9") (pin "1") (pinfunction "1_1") (pintype "passive"))
      (node (ref "IND1") (pin "1") (pinfunction "1_1") (pintype "passive"))
      (node (ref "IND2") (pin "1") (pinfunction "1_1") (pintype "passive"))
      (node (ref "R1") (pin "2") (pinfunction "2_2") (pintype "passive"))
      (node (ref "R12") (pin "1") (pinfunction "1_1") (pintype "passive"))
      (node (ref "R5") (pin "1") (pinfunction "1_1") (pintype "passive"))
      (node (ref "U2") (pin "14") (pinfunction "VSS_14") (pintype "power_in"))
      (node (ref "U2") (pin "17") (pinfunction "VSS_17") (pintype "power_in"))
      (node (ref "U2") (pin "20") (pinfunction "VSS_20") (pintype "power_in"))
      (node (ref "U2") (pin "8") (pinfunction "VSS_8") (pintype "power_in"))
      (node (ref "U4") (pin "13") (pinfunction "MTDO_13") (pintype "passive"))
      (node (ref "U4") (pin "33") (pinfunction "GND_33") (pintype "power_in"))
      (node (ref "X1") (pin "2") (pinfunction "GND_2") (pintype "passive"))
      (node (ref "X1") (pin "4") (pinfunction "GND_4") (pintype "passive"))
      (node (ref "X2") (pin "2") (pinfunction "GND_2") (pintype "passive"))
      (node (ref "X2") (pin "4") (pinfunction "GND_4") (pintype "passive"))
    )
    (net (code "77") (name "unconnected-(U1-I2C1_SCL{slash}TIM4_CH1{slash}PB6-Pad58)") (class "Default")
      (node (ref "U1") (pin "58") (pinfunction "I2C1_SCL/TIM4_CH1/PB6_58") (pintype "passive"))
    )
    (net (code "78") (name "unconnected-(U1-I2C1_SDA{slash}TIM4_CH2{slash}PB7-Pad59)") (class "Default")
      (node (ref "U1") (pin "59") (pinfunction "I2C1_SDA/TIM4_CH2/PB7_59") (pintype "passive"))
    )
    (net (code "79") (name "unconnected-(U1-I2C3_SCL{slash}TIM1_CH1{slash}PA8-Pad41)") (class "Default")
      (node (ref "U1") (pin "41") (pinfunction "I2C3_SCL/TIM1_CH1/PA8_41") (pintype "passive"))
    )
    (net (code "80") (name "unconnected-(U1-I2C3_SDA{slash}TIM3_CH4{slash}PC9-Pad40)") (class "Default")
      (node (ref "U1") (pin "40") (pinfunction "I2C3_SDA/TIM3_CH4/PC9_40") (pintype "passive"))
    )
    (net (code "81") (name "unconnected-(U1-PB0{slash}ADC_IN8{slash}TIM3_CH3-Pad26)") (class "Default")
      (node (ref "U1") (pin "26") (pinfunction "PB0/ADC_IN8/TIM3_CH3_26") (pintype "passive"))
    )
    (net (code "82") (name "unconnected-(U1-PB1{slash}ADC_IN9{slash}TIM3_CH4-Pad27)") (class "Default")
      (node (ref "U1") (pin "27") (pinfunction "PB1/ADC_IN9/TIM3_CH4_27") (pintype "passive"))
    )
    (net (code "83") (name "unconnected-(U1-PB4-Pad56)") (class "Default")
      (node (ref "U1") (pin "56") (pinfunction "PB4_56") (pintype "passive"))
    )
    (net (code "84") (name "unconnected-(U1-PB5-Pad57)") (class "Default")
      (node (ref "U1") (pin "57") (pinfunction "PB5_57") (pintype "passive"))
    )
    (net (code "85") (name "unconnected-(U1-PC0{slash}ADC_IN10-Pad8)") (class "Default")
      (node (ref "U1") (pin "8") (pinfunction "PC0/ADC_IN10_8") (pintype "passive"))
    )
    (net (code "86") (name "unconnected-(U1-PC1{slash}ADC_IN11-Pad9)") (class "Default")
      (node (ref "U1") (pin "9") (pinfunction "PC1/ADC_IN11_9") (pintype "passive"))
    )
    (net (code "87") (name "unconnected-(U1-PC2{slash}ADC_IN12-Pad10)") (class "Default")
      (node (ref "U1") (pin "10") (pinfunction "PC2/ADC_IN12_10") (pintype "passive"))
    )
    (net (code "88") (name "unconnected-(U1-PC3{slash}ADC_IN13-Pad11)") (class "Default")
      (node (ref "U1") (pin "11") (pinfunction "PC3/ADC_IN13_11") (pintype "passive"))
    )
    (net (code "89") (name "unconnected-(U1-PC13-Pad2)") (class "Default")
      (node (ref "U1") (pin "2") (pinfunction "PC13_2") (pintype "passive"))
    )
    (net (code "90") (name "unconnected-(U1-PC14{slash}OSC32_IN-Pad3)") (class "Default")
      (node (ref "U1") (pin "3") (pinfunction "PC14/OSC32_IN_3") (pintype "passive"))
    )
    (net (code "91") (name "unconnected-(U1-PC15{slash}OSC32_OUT-Pad4)") (class "Default")
      (node (ref "U1") (pin "4") (pinfunction "PC15/OSC32_OUT_4") (pintype "passive"))
    )
    (net (code "92") (name "unconnected-(U1-SPI2_MOSI{slash}PB15-Pad36)") (class "Default")
      (node (ref "U1") (pin "36") (pinfunction "SPI2_MOSI/PB15_36") (pintype "passive"))
    )
    (net (code "93") (name "unconnected-(U1-TIM3_CH3{slash}PC8-Pad39)") (class "Default")
      (node (ref "U1") (pin "39") (pinfunction "TIM3_CH3/PC8_39") (pintype "passive"))
    )
    (net (code "94") (name "unconnected-(U1-TIM4_CH3{slash}PB8-Pad61)") (class "Default")
      (node (ref "U1") (pin "61") (pinfunction "TIM4_CH3/PB8_61") (pintype "passive"))
    )
    (net (code "95") (name "unconnected-(U1-TIM4_CH4{slash}PB9-Pad62)") (class "Default")
      (node (ref "U1") (pin "62") (pinfunction "TIM4_CH4/PB9_62") (pintype "passive"))
    )
    (net (code "96") (name "unconnected-(U2-INR-Pad6)") (class "Default")
      (node (ref "U2") (pin "6") (pinfunction "INR_6") (pintype "power_in"))
    )
    (net (code "97") (name "unconnected-(U4-CPIO5-Pad24)") (class "Default")
      (node (ref "U4") (pin "24") (pinfunction "CPIO5_24") (pintype "power_in"))
    )
    (net (code "98") (name "unconnected-(U4-GPIO4-Pad16)") (class "Default")
      (node (ref "U4") (pin "16") (pinfunction "GPIO4_16") (pintype "power_in"))
    )
    (net (code "99") (name "unconnected-(U4-MTCK-Pad12)") (class "Default")
      (node (ref "U4") (pin "12") (pinfunction "MTCK_12") (pintype "passive"))
    )
    (net (code "100") (name "unconnected-(U4-MTMS-Pad9)") (class "Default")
      (node (ref "U4") (pin "9") (pinfunction "MTMS_9") (pintype "power_in"))
    )
    (net (code "101") (name "unconnected-(U4-MTOI-Pad10)") (class "Default")
      (node (ref "U4") (pin "10") (pinfunction "MTOI_10") (pintype "power_in"))
    )
    (net (code "102") (name "unconnected-(U4-SD_CLK-Pad21)") (class "Default")
      (node (ref "U4") (pin "21") (pinfunction "SD_CLK_21") (pintype "power_in"))
    )
    (net (code "103") (name "unconnected-(U4-SD_CMD-Pad20)") (class "Default")
      (node (ref "U4") (pin "20") (pinfunction "SD_CMD_20") (pintype "power_in"))
    )
    (net (code "104") (name "unconnected-(U4-SD_DATA_0-Pad22)") (class "Default")
      (node (ref "U4") (pin "22") (pinfunction "SD_DATA_0_22") (pintype "power_in"))
    )
    (net (code "105") (name "unconnected-(U4-SD_DATA_1-Pad23)") (class "Default")
      (node (ref "U4") (pin "23") (pinfunction "SD_DATA_1_23") (pintype "power_in"))
    )
    (net (code "106") (name "unconnected-(U4-SD_DATA_2-Pad18)") (class "Default")
      (node (ref "U4") (pin "18") (pinfunction "SD_DATA_2_18") (pintype "power_in"))
    )
    (net (code "107") (name "unconnected-(U4-SD_DATA_3-Pad19)") (class "Default")
      (node (ref "U4") (pin "19") (pinfunction "SD_DATA_3_19") (pintype "power_in"))
    )
    (net (code "108") (name "unconnected-(U4-TOUT-Pad6)") (class "Default")
      (node (ref "U4") (pin "6") (pinfunction "TOUT_6") (pintype "power_in"))
    )
    (net (code "109") (name "unconnected-(U4-VDD_RTS-Pad5)") (class "Default")
      (node (ref "U4") (pin "5") (pinfunction "VDD_RTS_5") (pintype "power_in"))
    )
    (net (code "110") (name "unconnected-(U4-XPD_DCDC-Pad8)") (class "Default")
      (node (ref "U4") (pin "8") (pinfunction "XPD_DCDC_8") (pintype "power_in"))
    )
    (net (code "111") (name "unconnected-(U7-FSYNC-Pad11)") (class "Default")
      (node (ref "U7") (pin "11") (pinfunction "FSYNC_11") (pintype "passive+no_connect"))
    )
    (net (code "112") (name "unconnected-(U7-INT-Pad12)") (class "Default")
      (node (ref "U7") (pin "12") (pinfunction "INT_12") (pintype "passive"))
    )
    (net (code "113") (name "unconnected-(USB1-ID-Pad4)") (class "Default")
      (node (ref "USB1") (pin "4") (pinfunction "ID_4") (pintype "passive"))
    )
    (net (code "114") (name "unconnected-(USB1-Pad6)") (class "Default")
      (node (ref "USB1") (pin "6") (pinfunction "6_6") (pintype "passive"))
    )
    (net (code "115") (name "unconnected-(USB1-Pad7)") (class "Default")
      (node (ref "USB1") (pin "7") (pinfunction "7_7") (pintype "passive"))
    )
  )
)
